# quadcopter.net
KiCad netlist of a schematic drawn in EAGLE
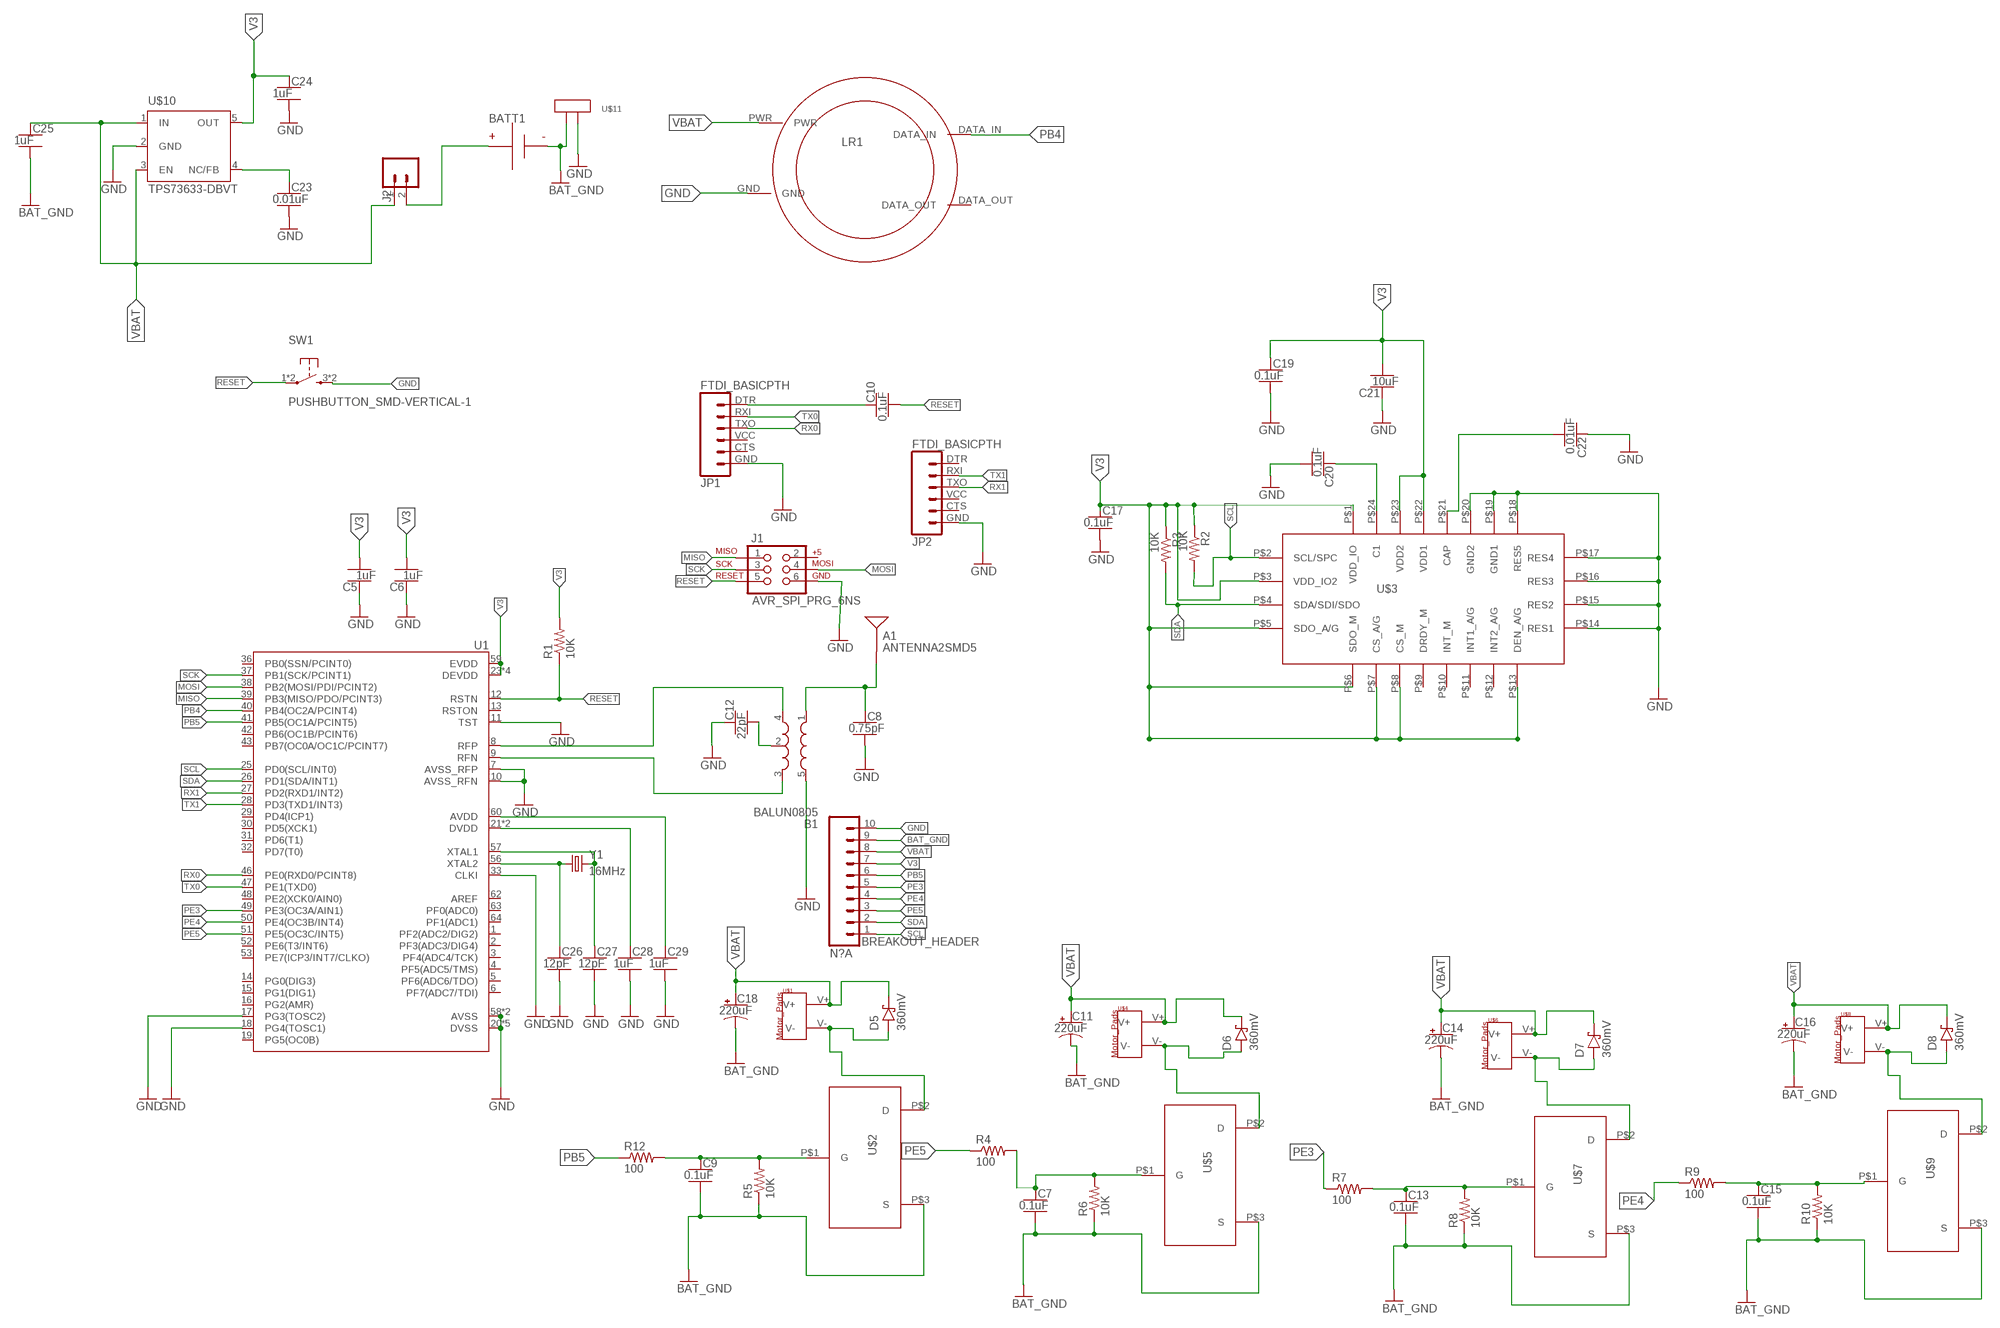
[diagram p0: schematic, sheet 1]

(export (version "E")
  (design (tool "Eeschema 10.0.6"))
  (components
    (comp (ref "A1")
      (value "ANTENNA2SMD5")
      (footprint "eagle-import:ANTENNA-CHIP5")
      (fields (field (name "MFR") "Linx Technologies Inc.") (field (name "MPN") "ANT-2.45-CHP-T"))
      (libsource (lib "eagle-import") (part "ANTENNA2SMD5"))
    )
    (comp (ref "B1")
      (value "BALUN0805")
      (footprint "eagle-import:BALUN")
      (fields (field (name "MFR") "Wurth Electronics Inc") (field (name "MPN") "748421245"))
      (libsource (lib "eagle-import") (part "BALUN0805"))
    )
    (comp (ref "BATT1")
      (value "BATTERY-HUBSAN-W/HOLDER")
      (footprint "eagle-import:BATTERY-W_HOLDER-380MAH-HUBSAN")
      (fields
        (field (name "MFR") "HUBSAN")
        (field (name "MPN") "X4-H107C-8-in-1")
        (field (name "CREATOR") "Swanson")
      )
      (libsource (lib "eagle-import") (part "BATTERY-HUBSAN-W/HOLDER"))
    )
    (comp (ref "BREAKOUT_HEADER")
      (value "N?A")
      (footprint "eagle-import:HDRV10W63P254_10X1_2540X254H838_HS")
      (fields (field (name "MFR") "Amphenol FCI") (field (name "MPN") "68000-110HLF"))
      (libsource (lib "eagle-import") (part "SIP-10_TH-254X10"))
    )
    (comp (ref "C5")
      (value "1uF")
      (footprint "eagle-import:CAPC2012X140_HS")
      (fields
        (field (name "MFR") "Murata Electronics North America")
        (field (name "MPN") "GRM21BR71H105KA12L")
      )
      (libsource (lib "eagle-import") (part "CAPACITOR-NP_SMD-2012-0805_CERAMIC-1UF"))
    )
    (comp (ref "C6")
      (value "1uF")
      (footprint "eagle-import:CAPC2012X140_HS")
      (fields
        (field (name "MFR") "Murata Electronics North America")
        (field (name "MPN") "GRM21BR71H105KA12L")
      )
      (libsource (lib "eagle-import") (part "CAPACITOR-NP_SMD-2012-0805_CERAMIC-1UF"))
    )
    (comp (ref "C7")
      (value "0.1uF")
      (footprint "eagle-import:CERAMIC_CAP_0805")
      (fields
        (field (name "MFR") "Murata Electronics North America")
        (field (name "MPN") "GRM21BR71H104KA01L")
        (field (name "CREATOR") "SWANSON")
      )
      (libsource (lib "eagle-import") (part "CERAMIC_CAP-0805-0.1UF"))
    )
    (comp (ref "C8")
      (value "0.75pF")
      (footprint "eagle-import:CAPC2012X140_HS")
      (fields
        (field (name "MFR") "Murata Electronics North America")
        (field (name "MPN") "GQM2195C2AR75CB01D")
      )
      (libsource (lib "eagle-import") (part "CAPACITOR-NP_SMD-2012-0805_CERAMIC-0.75PF"))
    )
    (comp (ref "C9")
      (value "0.1uF")
      (footprint "eagle-import:CERAMIC_CAP_0805")
      (fields
        (field (name "MFR") "Murata Electronics North America")
        (field (name "MPN") "GRM21BR71H104KA01L")
        (field (name "CREATOR") "SWANSON")
      )
      (libsource (lib "eagle-import") (part "CERAMIC_CAP-0805-0.1UF"))
    )
    (comp (ref "C10")
      (value "0.1uF")
      (footprint "eagle-import:CAPC2012X140_HS")
      (fields
        (field (name "MFR") "Murata Electronics North America")
        (field (name "MPN") "GRM21BR71H104KA01L")
      )
      (libsource (lib "eagle-import") (part "CAPACITOR-NP_SMD-2012-0805_CERAMIC-0.1UF"))
    )
    (comp (ref "C11")
      (value "220uF")
      (footprint "eagle-import:CAPMP7343X310_HS")
      (fields (field (name "MFR") "AVX Corporation") (field (name "MPN") "TAJD227K006RNJ"))
      (libsource (lib "eagle-import") (part "CAPACITOR-POL_SMD-7043-D_TANTALUM-220UF"))
    )
    (comp (ref "C12")
      (value "22pF")
      (footprint "eagle-import:CAPC2012X140_HS")
      (fields
        (field (name "MFR") "Murata Electronics North America")
        (field (name "MPN") "GRM21A5C2E220JW01D")
      )
      (libsource (lib "eagle-import") (part "CAPACITOR-NP_SMD-2012-0805_CERAMIC-22PF"))
    )
    (comp (ref "C13")
      (value "0.1uF")
      (footprint "eagle-import:CERAMIC_CAP_0805")
      (fields
        (field (name "MFR") "Murata Electronics North America")
        (field (name "MPN") "GRM21BR71H104KA01L")
        (field (name "CREATOR") "SWANSON")
      )
      (libsource (lib "eagle-import") (part "CERAMIC_CAP-0805-0.1UF"))
    )
    (comp (ref "C14")
      (value "220uF")
      (footprint "eagle-import:CAPMP7343X310_HS")
      (fields (field (name "MFR") "AVX Corporation") (field (name "MPN") "TAJD227K006RNJ"))
      (libsource (lib "eagle-import") (part "CAPACITOR-POL_SMD-7043-D_TANTALUM-220UF"))
    )
    (comp (ref "C15")
      (value "0.1uF")
      (footprint "eagle-import:CERAMIC_CAP_0805")
      (fields
        (field (name "MFR") "Murata Electronics North America")
        (field (name "MPN") "GRM21BR71H104KA01L")
        (field (name "CREATOR") "SWANSON")
      )
      (libsource (lib "eagle-import") (part "CERAMIC_CAP-0805-0.1UF"))
    )
    (comp (ref "C16")
      (value "220uF")
      (footprint "eagle-import:CAPMP7343X310_HS")
      (fields (field (name "MFR") "AVX Corporation") (field (name "MPN") "TAJD227K006RNJ"))
      (libsource (lib "eagle-import") (part "CAPACITOR-POL_SMD-7043-D_TANTALUM-220UF"))
    )
    (comp (ref "C17")
      (value "0.1uF")
      (footprint "eagle-import:CAPC2012X140_HS")
      (fields
        (field (name "MFR") "Murata Electronics North America")
        (field (name "MPN") "GRM21BR71H104KA01L")
      )
      (libsource (lib "eagle-import") (part "CAPACITOR-NP_SMD-2012-0805_CERAMIC-0.1UF"))
    )
    (comp (ref "C18")
      (value "220uF")
      (footprint "eagle-import:CAPMP7343X310_HS")
      (fields (field (name "MFR") "AVX Corporation") (field (name "MPN") "TAJD227K006RNJ"))
      (libsource (lib "eagle-import") (part "CAPACITOR-POL_SMD-7043-D_TANTALUM-220UF"))
    )
    (comp (ref "C19")
      (value "0.1uF")
      (footprint "eagle-import:CAPC2012X140_HS")
      (fields
        (field (name "MFR") "Murata Electronics North America")
        (field (name "MPN") "GRM21BR71H104KA01L")
      )
      (libsource (lib "eagle-import") (part "CAPACITOR-NP_SMD-2012-0805_CERAMIC-0.1UF"))
    )
    (comp (ref "C20")
      (value "0.1uF")
      (footprint "eagle-import:CAPC2012X140_HS")
      (fields
        (field (name "MFR") "Murata Electronics North America")
        (field (name "MPN") "GRM21BR71H104KA01L")
      )
      (libsource (lib "eagle-import") (part "CAPACITOR-NP_SMD-2012-0805_CERAMIC-0.1UF"))
    )
    (comp (ref "C21")
      (value "10uF")
      (footprint "eagle-import:CAPC2012X140_HS")
      (fields
        (field (name "MFR") "Murata Electronics North America")
        (field (name "MPN") "GRM21BR61E106KA73L")
      )
      (libsource (lib "eagle-import") (part "CAPACITOR-NP_SMD-2012-0805_CERAMIC-10UF"))
    )
    (comp (ref "C22")
      (value "0.01uF")
      (footprint "eagle-import:CAPC2012X140_HS")
      (fields
        (field (name "MFR") "Murata Electronics North America")
        (field (name "MPN") "GRM2195C1H103FA01D")
      )
      (libsource (lib "eagle-import") (part "CAPACITOR-NP_SMD-2012-0805_CERAMIC-0.01UF"))
    )
    (comp (ref "C23")
      (value "0.01uF")
      (footprint "eagle-import:CAPC2012X140_HS")
      (fields
        (field (name "MFR") "Murata Electronics North America")
        (field (name "MPN") "GRM2195C1H103FA01D")
      )
      (libsource (lib "eagle-import") (part "CAPACITOR-NP_SMD-2012-0805_CERAMIC-0.01UF"))
    )
    (comp (ref "C24")
      (value "1uF")
      (footprint "eagle-import:CAPC2012X140_HS")
      (fields
        (field (name "MFR") "Murata Electronics North America")
        (field (name "MPN") "GRM21BR71H105KA12L")
      )
      (libsource (lib "eagle-import") (part "CAPACITOR-NP_SMD-2012-0805_CERAMIC-1UF"))
    )
    (comp (ref "C25")
      (value "1uF")
      (footprint "eagle-import:CAPC2012X140_HS")
      (fields
        (field (name "MFR") "Murata Electronics North America")
        (field (name "MPN") "GRM21BR71H105KA12L")
      )
      (libsource (lib "eagle-import") (part "CAPACITOR-NP_SMD-2012-0805_CERAMIC-1UF"))
    )
    (comp (ref "C26")
      (value "12pF")
      (footprint "eagle-import:CAPC2012X140_HS")
      (fields
        (field (name "MFR") "Murata Electronics North America")
        (field (name "MPN") "GRM21A5C2E120JW01D")
      )
      (libsource (lib "eagle-import") (part "CAPACITOR-NP_SMD-2012-0805_CERAMIC-12PF"))
    )
    (comp (ref "C27")
      (value "12pF")
      (footprint "eagle-import:CAPC2012X140_HS")
      (fields
        (field (name "MFR") "Murata Electronics North America")
        (field (name "MPN") "GRM21A5C2E120JW01D")
      )
      (libsource (lib "eagle-import") (part "CAPACITOR-NP_SMD-2012-0805_CERAMIC-12PF"))
    )
    (comp (ref "C28")
      (value "1uF")
      (footprint "eagle-import:CAPC2012X140_HS")
      (fields
        (field (name "MFR") "Murata Electronics North America")
        (field (name "MPN") "GRM21BR71H105KA12L")
      )
      (libsource (lib "eagle-import") (part "CAPACITOR-NP_SMD-2012-0805_CERAMIC-1UF"))
    )
    (comp (ref "C29")
      (value "1uF")
      (footprint "eagle-import:CAPC2012X140_HS")
      (fields
        (field (name "MFR") "Murata Electronics North America")
        (field (name "MPN") "GRM21BR71H105KA12L")
      )
      (libsource (lib "eagle-import") (part "CAPACITOR-NP_SMD-2012-0805_CERAMIC-1UF"))
    )
    (comp (ref "D5")
      (value "360mV")
      (footprint "eagle-import:SOD3716X135_HS")
      (fields
        (field (name "MFR") "Toshiba Semiconductor and Storage")
        (field (name "MPN") "CRS08(TE85L,Q,M)")
      )
      (libsource (lib "eagle-import") (part "DIODE-SCHOTTKY_SMD-SOD123-360MV"))
    )
    (comp (ref "D6")
      (value "360mV")
      (footprint "eagle-import:SOD3716X135_HS")
      (fields
        (field (name "MFR") "Toshiba Semiconductor and Storage")
        (field (name "MPN") "CRS08(TE85L,Q,M)")
      )
      (libsource (lib "eagle-import") (part "DIODE-SCHOTTKY_SMD-SOD123-360MV"))
    )
    (comp (ref "D7")
      (value "360mV")
      (footprint "eagle-import:SOD3716X135_HS")
      (fields
        (field (name "MFR") "Toshiba Semiconductor and Storage")
        (field (name "MPN") "CRS08(TE85L,Q,M)")
      )
      (libsource (lib "eagle-import") (part "DIODE-SCHOTTKY_SMD-SOD123-360MV"))
    )
    (comp (ref "D8")
      (value "360mV")
      (footprint "eagle-import:SOD3716X135_HS")
      (fields
        (field (name "MFR") "Toshiba Semiconductor and Storage")
        (field (name "MPN") "CRS08(TE85L,Q,M)")
      )
      (libsource (lib "eagle-import") (part "DIODE-SCHOTTKY_SMD-SOD123-360MV"))
    )
    (comp (ref "J1")
      (value "AVR_SPI_PRG_6NS")
      (footprint "eagle-import:2X3-NS")
      (fields (field (name "MFR") "Amphenol FCI") (field (name "MPN") "67997-206HLF"))
      (libsource (lib "eagle-import") (part "AVR_SPI_PRG_6NS"))
    )
    (comp (ref "J2")
      (value "MALE_HEADER_2POS-2X1-0.1IN")
      (footprint "eagle-import:MALE_HEADER_2X1_0.1IN")
      (fields
        (field (name "MFR") "3M")
        (field (name "MPN") "961102-6404-AR")
        (field (name "CREATOR") "SWANSON")
      )
      (libsource (lib "eagle-import") (part "MALE_HEADER_2POS-2X1-0.1IN"))
    )
    (comp (ref "JP1")
      (value "FTDI_BASICPTH")
      (footprint "eagle-import:FTDI_BASIC")
      (fields (field (name "MFR") "Amphenol FCI") (field (name "MPN") "68016-406HLF"))
      (libsource (lib "eagle-import") (part "FTDI_BASICPTH"))
    )
    (comp (ref "JP2")
      (value "FTDI_BASICPTH")
      (footprint "eagle-import:FTDI_BASIC")
      (fields (field (name "MFR") "Amphenol FCI") (field (name "MPN") "68016-406HLF"))
      (libsource (lib "eagle-import") (part "FTDI_BASICPTH"))
    )
    (comp (ref "LR1")
      (value "LED_RING")
      (footprint "eagle-import:LED_RING")
      (fields
        (field (name "MFR") "Adafruit Industries LLC")
        (field (name "MPN") "1586")
        (field (name "CREATOR") "Zhe Wang")
      )
      (libsource (lib "eagle-import") (part "LED_RING"))
    )
    (comp (ref "R1")
      (value "10K")
      (footprint "eagle-import:RESC2012X60_HS")
      (fields (field (name "MFR") "Yageo") (field (name "MPN") "RC0805JR-0710KL"))
      (libsource (lib "eagle-import") (part "RESISTOR_SMD-2012-0805-10K"))
    )
    (comp (ref "R2")
      (value "10K")
      (footprint "eagle-import:RESC2012X60_HS")
      (fields (field (name "MFR") "Yageo") (field (name "MPN") "RC0805JR-0710KL"))
      (libsource (lib "eagle-import") (part "RESISTOR_SMD-2012-0805-10K"))
    )
    (comp (ref "R3")
      (value "10K")
      (footprint "eagle-import:RESC2012X60_HS")
      (fields (field (name "MFR") "Yageo") (field (name "MPN") "RC0805JR-0710KL"))
      (libsource (lib "eagle-import") (part "RESISTOR_SMD-2012-0805-10K"))
    )
    (comp (ref "R4")
      (value "100")
      (footprint "eagle-import:RESC2012X60_HS")
      (fields (field (name "MFR") "Yageo") (field (name "MPN") "RC0805JR-07100RL"))
      (libsource (lib "eagle-import") (part "RESISTOR_SMD-2012-0805-100"))
    )
    (comp (ref "R5")
      (value "10K")
      (footprint "eagle-import:RESC2012X60_HS")
      (fields (field (name "MFR") "Yageo") (field (name "MPN") "RC0805JR-0710KL"))
      (libsource (lib "eagle-import") (part "RESISTOR_SMD-2012-0805-10K"))
    )
    (comp (ref "R6")
      (value "10K")
      (footprint "eagle-import:RESC2012X60_HS")
      (fields (field (name "MFR") "Yageo") (field (name "MPN") "RC0805JR-0710KL"))
      (libsource (lib "eagle-import") (part "RESISTOR_SMD-2012-0805-10K"))
    )
    (comp (ref "R7")
      (value "100")
      (footprint "eagle-import:RESC2012X60_HS")
      (fields (field (name "MFR") "Yageo") (field (name "MPN") "RC0805JR-07100RL"))
      (libsource (lib "eagle-import") (part "RESISTOR_SMD-2012-0805-100"))
    )
    (comp (ref "R8")
      (value "10K")
      (footprint "eagle-import:RESC2012X60_HS")
      (fields (field (name "MFR") "Yageo") (field (name "MPN") "RC0805JR-0710KL"))
      (libsource (lib "eagle-import") (part "RESISTOR_SMD-2012-0805-10K"))
    )
    (comp (ref "R9")
      (value "100")
      (footprint "eagle-import:RESC2012X60_HS")
      (fields (field (name "MFR") "Yageo") (field (name "MPN") "RC0805JR-07100RL"))
      (libsource (lib "eagle-import") (part "RESISTOR_SMD-2012-0805-100"))
    )
    (comp (ref "R10")
      (value "10K")
      (footprint "eagle-import:RESC2012X60_HS")
      (fields (field (name "MFR") "Yageo") (field (name "MPN") "RC0805JR-0710KL"))
      (libsource (lib "eagle-import") (part "RESISTOR_SMD-2012-0805-10K"))
    )
    (comp (ref "R12")
      (value "100")
      (footprint "eagle-import:RESC2012X60_HS")
      (fields (field (name "MFR") "Yageo") (field (name "MPN") "RC0805JR-07100RL"))
      (libsource (lib "eagle-import") (part "RESISTOR_SMD-2012-0805-100"))
    )
    (comp (ref "SW1")
      (value "PUSHBUTTON_SMD-VERTICAL-1")
      (footprint "eagle-import:TE_FSM8JSMA_HS")
      (fields (field (name "MFR") "TE Connectivity Alcoswitch Switches") (field (name "MPN") "FSM4JSMA"))
      (libsource (lib "eagle-import") (part "PUSHBUTTON_SMD-VERTICAL-1"))
    )
    (comp (ref "U$1")
      (value "MOTOR_PADS")
      (footprint "eagle-import:MOTOR_PADS")
      (fields (field (name "MFR") "NA"))
      (libsource (lib "eagle-import") (part "MOTOR_PADS"))
    )
    (comp (ref "U$2")
      (value "N-CHANNEL_MOSFET")
      (footprint "eagle-import:N-CHANNELMOFSET")
      (fields
        (field (name "MFR") "Vishay Siliconix")
        (field (name "MPN") "SI2302CDS-T1-E3")
        (field (name "CREATOR") "Jason_Wong")
      )
      (libsource (lib "eagle-import") (part "N-CHANNEL_MOSFET"))
    )
    (comp (ref "U$3")
      (value "9-AXIS_IMU")
      (footprint "eagle-import:9-AXIS_IMU")
      (fields
        (field (name "MFR") "STMicroelectronics")
        (field (name "MPN") "LSM9DS1TR")
        (field (name "CREATOR") "Jason_Wong")
      )
      (libsource (lib "eagle-import") (part "9-AXIS_IMU"))
    )
    (comp (ref "U$4")
      (value "MOTOR_PADS")
      (footprint "eagle-import:MOTOR_PADS")
      (fields (field (name "MFR") "NA"))
      (libsource (lib "eagle-import") (part "MOTOR_PADS"))
    )
    (comp (ref "U$5")
      (value "N-CHANNEL_MOSFET")
      (footprint "eagle-import:N-CHANNELMOFSET")
      (fields
        (field (name "MFR") "Vishay Siliconix")
        (field (name "MPN") "SI2302CDS-T1-E3")
        (field (name "CREATOR") "Jason_Wong")
      )
      (libsource (lib "eagle-import") (part "N-CHANNEL_MOSFET"))
    )
    (comp (ref "U$6")
      (value "MOTOR_PADS")
      (footprint "eagle-import:MOTOR_PADS")
      (fields (field (name "MFR") "NA"))
      (libsource (lib "eagle-import") (part "MOTOR_PADS"))
    )
    (comp (ref "U$7")
      (value "N-CHANNEL_MOSFET")
      (footprint "eagle-import:N-CHANNELMOFSET")
      (fields
        (field (name "MFR") "Vishay Siliconix")
        (field (name "MPN") "SI2302CDS-T1-E3")
        (field (name "CREATOR") "Jason_Wong")
      )
      (libsource (lib "eagle-import") (part "N-CHANNEL_MOSFET"))
    )
    (comp (ref "U$8")
      (value "MOTOR_PADS")
      (footprint "eagle-import:MOTOR_PADS")
      (fields (field (name "MFR") "NA"))
      (libsource (lib "eagle-import") (part "MOTOR_PADS"))
    )
    (comp (ref "U$9")
      (value "N-CHANNEL_MOSFET")
      (footprint "eagle-import:N-CHANNELMOFSET")
      (fields
        (field (name "MFR") "Vishay Siliconix")
        (field (name "MPN") "SI2302CDS-T1-E3")
        (field (name "CREATOR") "Jason_Wong")
      )
      (libsource (lib "eagle-import") (part "N-CHANNEL_MOSFET"))
    )
    (comp (ref "U$10")
      (value "TPS73633-DBVT")
      (footprint "eagle-import:SOT23-DBV")
      (fields (field (name "MFR") "Texas Instruments") (field (name "MPN") "LP3985IM5X-3.0/NOPB"))
      (libsource (lib "eagle-import") (part "TPS73633-DBVT"))
    )
    (comp (ref "U$11")
      (value "NET_BRIDGE")
      (footprint "eagle-import:NET_BRIDGE")
      (fields
        (field (name "MFR") "NONE")
        (field (name "MPN") "123-456-789")
        (field (name "CREATOR") "Zhe")
        (field (name "REVIEWER") "NONE")
      )
      (libsource (lib "eagle-import") (part "NET_BRIDGE"))
    )
    (comp (ref "U1")
      (value "ATMEGA128RFA1")
      (footprint "eagle-import:QFN-64")
      (fields
        (field (name "MFR") "Atmel")
        (field (name "MPN") "ATMEGA128RFA1-ZUR00")
        (field (name "CREATOR") "Swanson")
      )
      (libsource (lib "eagle-import") (part "ATMEGA128RFA1"))
    )
    (comp (ref "Y1")
      (value "16MHz")
      (footprint "eagle-import:CRYSTAL-SMD-5X3")
      (fields (field (name "MFR") "Abracon LLC") (field (name "MPN") "ABM3B-16.000MHZ-B2-T"))
      (libsource (lib "eagle-import") (part "CRYSTAL5X3"))
    )
  )
  (nets
    (net (code "1") (name "BAT_GND") (class "Default")
      (node (ref "BATT1") (pin "-") (pinfunction "N_-") (pintype "bidirectional"))
      (node (ref "BREAKOUT_HEADER") (pin "9") (pinfunction "9_9") (pintype "passive"))
      (node (ref "C11") (pin "2") (pinfunction "-_2") (pintype "passive"))
      (node (ref "C13") (pin "2") (pinfunction "2_2") (pintype "passive"))
      (node (ref "C14") (pin "2") (pinfunction "-_2") (pintype "passive"))
      (node (ref "C15") (pin "2") (pinfunction "2_2") (pintype "passive"))
      (node (ref "C16") (pin "2") (pinfunction "-_2") (pintype "passive"))
      (node (ref "C18") (pin "2") (pinfunction "-_2") (pintype "passive"))
      (node (ref "C25") (pin "2") (pinfunction "2_2") (pintype "passive"))
      (node (ref "C7") (pin "2") (pinfunction "2_2") (pintype "passive"))
      (node (ref "C9") (pin "2") (pinfunction "2_2") (pintype "passive"))
      (node (ref "R10") (pin "1") (pinfunction "1_1") (pintype "passive"))
      (node (ref "R5") (pin "1") (pinfunction "1_1") (pintype "passive"))
      (node (ref "R6") (pin "1") (pinfunction "1_1") (pintype "passive"))
      (node (ref "R8") (pin "1") (pinfunction "1_1") (pintype "passive"))
      (node (ref "U$11") (pin "P$1") (pinfunction "P$1_P$1") (pintype "bidirectional"))
      (node (ref "U$2") (pin "P$3") (pinfunction "S_P$3") (pintype "bidirectional"))
      (node (ref "U$5") (pin "P$3") (pinfunction "S_P$3") (pintype "bidirectional"))
      (node (ref "U$7") (pin "P$3") (pinfunction "S_P$3") (pintype "bidirectional"))
      (node (ref "U$9") (pin "P$3") (pinfunction "S_P$3") (pintype "bidirectional"))
    )
    (net (code "2") (name "GND") (class "Default")
      (node (ref "B1") (pin "5") (pinfunction "GND_5") (pintype "bidirectional"))
      (node (ref "BREAKOUT_HEADER") (pin "10") (pinfunction "10_10") (pintype "passive"))
      (node (ref "C12") (pin "1") (pinfunction "1_1") (pintype "passive"))
      (node (ref "C17") (pin "2") (pinfunction "2_2") (pintype "passive"))
      (node (ref "C19") (pin "2") (pinfunction "2_2") (pintype "passive"))
      (node (ref "C20") (pin "2") (pinfunction "2_2") (pintype "passive"))
      (node (ref "C21") (pin "1") (pinfunction "1_1") (pintype "passive"))
      (node (ref "C22") (pin "1") (pinfunction "1_1") (pintype "passive"))
      (node (ref "C23") (pin "2") (pinfunction "2_2") (pintype "passive"))
      (node (ref "C24") (pin "2") (pinfunction "2_2") (pintype "passive"))
      (node (ref "C26") (pin "2") (pinfunction "2_2") (pintype "passive"))
      (node (ref "C27") (pin "2") (pinfunction "2_2") (pintype "passive"))
      (node (ref "C28") (pin "2") (pinfunction "2_2") (pintype "passive"))
      (node (ref "C29") (pin "2") (pinfunction "2_2") (pintype "passive"))
      (node (ref "C5") (pin "1") (pinfunction "1_1") (pintype "passive"))
      (node (ref "C6") (pin "1") (pinfunction "1_1") (pintype "passive"))
      (node (ref "C8") (pin "2") (pinfunction "2_2") (pintype "passive"))
      (node (ref "J1") (pin "6") (pinfunction "6_6") (pintype "passive"))
      (node (ref "JP1") (pin "GND") (pinfunction "6_GND") (pintype "passive"))
      (node (ref "JP2") (pin "GND") (pinfunction "6_GND") (pintype "passive"))
      (node (ref "LR1") (pin "GND") (pinfunction "GND_GND") (pintype "bidirectional"))
      (node (ref "SW1") (pin "3") (pinfunction "2_3") (pintype "passive"))
      (node (ref "SW1") (pin "4") (pinfunction "2_4") (pintype "passive"))
      (node (ref "U$10") (pin "2") (pinfunction "GND_2") (pintype "input"))
      (node (ref "U$11") (pin "P$2") (pinfunction "P$2_P$2") (pintype "bidirectional"))
      (node (ref "U$3") (pin "P$14") (pinfunction "RES1_P$14") (pintype "bidirectional"))
      (node (ref "U$3") (pin "P$15") (pinfunction "RES2_P$15") (pintype "bidirectional"))
      (node (ref "U$3") (pin "P$16") (pinfunction "RES3_P$16") (pintype "bidirectional"))
      (node (ref "U$3") (pin "P$17") (pinfunction "RES4_P$17") (pintype "bidirectional"))
      (node (ref "U$3") (pin "P$18") (pinfunction "RES5_P$18") (pintype "bidirectional"))
      (node (ref "U$3") (pin "P$19") (pinfunction "GND1_P$19") (pintype "bidirectional"))
      (node (ref "U$3") (pin "P$20") (pinfunction "GND2_P$20") (pintype "bidirectional"))
      (node (ref "U1") (pin "10") (pinfunction "AVSS_RFN_10") (pintype "bidirectional"))
      (node (ref "U1") (pin "11") (pinfunction "TST_11") (pintype "bidirectional"))
      (node (ref "U1") (pin "17") (pinfunction "PG3(TOSC2)_17") (pintype "bidirectional"))
      (node (ref "U1") (pin "18") (pinfunction "PG4(TOSC1)_18") (pintype "bidirectional"))
      (node (ref "U1") (pin "20") (pinfunction "DVSS_20") (pintype "bidirectional"))
      (node (ref "U1") (pin "24") (pinfunction "DVSS_24") (pintype "bidirectional"))
      (node (ref "U1") (pin "33") (pinfunction "CLKI_33") (pintype "bidirectional"))
      (node (ref "U1") (pin "35") (pinfunction "DVSS_35") (pintype "bidirectional"))
      (node (ref "U1") (pin "45") (pinfunction "DVSS_45") (pintype "bidirectional"))
      (node (ref "U1") (pin "55") (pinfunction "DVSS_55") (pintype "bidirectional"))
      (node (ref "U1") (pin "58") (pinfunction "AVSS_58") (pintype "bidirectional"))
      (node (ref "U1") (pin "61") (pinfunction "AVSS_61") (pintype "bidirectional"))
      (node (ref "U1") (pin "7") (pinfunction "AVSS_RFP_7") (pintype "bidirectional"))
    )
    (net (code "3") (name "MISO") (class "Default")
      (node (ref "J1") (pin "1") (pinfunction "1_1") (pintype "passive"))
      (node (ref "U1") (pin "39") (pinfunction "PB3(MISO/PDO/PCINT3)_39") (pintype "bidirectional"))
    )
    (net (code "4") (name "MOSI") (class "Default")
      (node (ref "J1") (pin "4") (pinfunction "4_4") (pintype "passive"))
      (node (ref "U1") (pin "38") (pinfunction "PB2(MOSI/PDI/PCINT2)_38") (pintype "bidirectional"))
    )
    (net (code "5") (name "Net-(A1-SIGNAL)") (class "Default")
      (node (ref "A1") (pin "FEED") (pinfunction "SIGNAL_FEED") (pintype "bidirectional"))
      (node (ref "B1") (pin "1") (pinfunction "IN_1") (pintype "bidirectional"))
      (node (ref "C8") (pin "1") (pinfunction "1_1") (pintype "passive"))
    )
    (net (code "6") (name "Net-(B1-GND-Pad2)") (class "Default")
      (node (ref "B1") (pin "2") (pinfunction "GND_2") (pintype "bidirectional"))
      (node (ref "C12") (pin "2") (pinfunction "2_2") (pintype "passive"))
    )
    (net (code "7") (name "Net-(B1-OUT1)") (class "Default")
      (node (ref "B1") (pin "4") (pinfunction "OUT1_4") (pintype "bidirectional"))
      (node (ref "U1") (pin "8") (pinfunction "RFP_8") (pintype "bidirectional"))
    )
    (net (code "8") (name "Net-(B1-OUT2)") (class "Default")
      (node (ref "B1") (pin "3") (pinfunction "OUT2_3") (pintype "bidirectional"))
      (node (ref "U1") (pin "9") (pinfunction "RFN_9") (pintype "bidirectional"))
    )
    (net (code "9") (name "Net-(BATT1-P)") (class "Default")
      (node (ref "BATT1") (pin "+") (pinfunction "P_+") (pintype "bidirectional"))
      (node (ref "J2") (pin "2") (pinfunction "2_2") (pintype "passive"))
    )
    (net (code "10") (name "Net-(C28-Pad1)") (class "Default")
      (node (ref "C28") (pin "1") (pinfunction "1_1") (pintype "passive"))
      (node (ref "U1") (pin "21") (pinfunction "DVDD_21") (pintype "bidirectional"))
      (node (ref "U1") (pin "22") (pinfunction "DVDD_22") (pintype "bidirectional"))
    )
    (net (code "11") (name "Net-(JP1-1)") (class "Default")
      (node (ref "C10") (pin "1") (pinfunction "1_1") (pintype "passive"))
      (node (ref "JP1") (pin "DTR") (pinfunction "1_DTR") (pintype "passive"))
    )
    (net (code "12") (name "Net-(U$2-D)") (class "Default")
      (node (ref "D5") (pin "A") (pinfunction "A_A") (pintype "passive"))
      (node (ref "U$1") (pin "V-") (pinfunction "V-_V-") (pintype "bidirectional"))
      (node (ref "U$2") (pin "P$2") (pinfunction "D_P$2") (pintype "bidirectional"))
    )
    (net (code "13") (name "Net-(U$2-G)") (class "Default")
      (node (ref "C9") (pin "1") (pinfunction "1_1") (pintype "passive"))
      (node (ref "R12") (pin "2") (pinfunction "2_2") (pintype "passive"))
      (node (ref "R5") (pin "2") (pinfunction "2_2") (pintype "passive"))
      (node (ref "U$2") (pin "P$1") (pinfunction "G_P$1") (pintype "bidirectional"))
    )
    (net (code "14") (name "Net-(U$3-C1)") (class "Default")
      (node (ref "C20") (pin "1") (pinfunction "1_1") (pintype "passive"))
      (node (ref "U$3") (pin "P$24") (pinfunction "C1_P$24") (pintype "bidirectional"))
    )
    (net (code "15") (name "Net-(U$3-CAP)") (class "Default")
      (node (ref "C22") (pin "2") (pinfunction "2_2") (pintype "passive"))
      (node (ref "U$3") (pin "P$21") (pinfunction "CAP_P$21") (pintype "bidirectional"))
    )
    (net (code "16") (name "Net-(U$5-D)") (class "Default")
      (node (ref "D6") (pin "A") (pinfunction "A_A") (pintype "passive"))
      (node (ref "U$4") (pin "V-") (pinfunction "V-_V-") (pintype "bidirectional"))
      (node (ref "U$5") (pin "P$2") (pinfunction "D_P$2") (pintype "bidirectional"))
    )
    (net (code "17") (name "Net-(U$5-G)") (class "Default")
      (node (ref "C7") (pin "1") (pinfunction "1_1") (pintype "passive"))
      (node (ref "R4") (pin "2") (pinfunction "2_2") (pintype "passive"))
      (node (ref "R6") (pin "2") (pinfunction "2_2") (pintype "passive"))
      (node (ref "U$5") (pin "P$1") (pinfunction "G_P$1") (pintype "bidirectional"))
    )
    (net (code "18") (name "Net-(U$7-D)") (class "Default")
      (node (ref "D7") (pin "A") (pinfunction "A_A") (pintype "passive"))
      (node (ref "U$6") (pin "V-") (pinfunction "V-_V-") (pintype "bidirectional"))
      (node (ref "U$7") (pin "P$2") (pinfunction "D_P$2") (pintype "bidirectional"))
    )
    (net (code "19") (name "Net-(U$7-G)") (class "Default")
      (node (ref "C13") (pin "1") (pinfunction "1_1") (pintype "passive"))
      (node (ref "R7") (pin "2") (pinfunction "2_2") (pintype "passive"))
      (node (ref "R8") (pin "2") (pinfunction "2_2") (pintype "passive"))
      (node (ref "U$7") (pin "P$1") (pinfunction "G_P$1") (pintype "bidirectional"))
    )
    (net (code "20") (name "Net-(U$9-D)") (class "Default")
      (node (ref "D8") (pin "A") (pinfunction "A_A") (pintype "passive"))
      (node (ref "U$8") (pin "V-") (pinfunction "V-_V-") (pintype "bidirectional"))
      (node (ref "U$9") (pin "P$2") (pinfunction "D_P$2") (pintype "bidirectional"))
    )
    (net (code "21") (name "Net-(U$9-G)") (class "Default")
      (node (ref "C15") (pin "1") (pinfunction "1_1") (pintype "passive"))
      (node (ref "R10") (pin "2") (pinfunction "2_2") (pintype "passive"))
      (node (ref "R9") (pin "2") (pinfunction "2_2") (pintype "passive"))
      (node (ref "U$9") (pin "P$1") (pinfunction "G_P$1") (pintype "bidirectional"))
    )
    (net (code "22") (name "Net-(U$10-NC{slash}FB)") (class "Default")
      (node (ref "C23") (pin "1") (pinfunction "1_1") (pintype "passive"))
      (node (ref "U$10") (pin "4") (pinfunction "NC/FB_4") (pintype "passive"))
    )
    (net (code "23") (name "Net-(U1-AVDD)") (class "Default")
      (node (ref "C29") (pin "1") (pinfunction "1_1") (pintype "passive"))
      (node (ref "U1") (pin "60") (pinfunction "AVDD_60") (pintype "bidirectional"))
    )
    (net (code "24") (name "Net-(U1-XTAL1)") (class "Default")
      (node (ref "C27") (pin "1") (pinfunction "1_1") (pintype "passive"))
      (node (ref "U1") (pin "57") (pinfunction "XTAL1_57") (pintype "bidirectional"))
      (node (ref "Y1") (pin "3") (pinfunction "2_3") (pintype "passive"))
    )
    (net (code "25") (name "Net-(U1-XTAL2)") (class "Default")
      (node (ref "C26") (pin "1") (pinfunction "1_1") (pintype "passive"))
      (node (ref "U1") (pin "56") (pinfunction "XTAL2_56") (pintype "bidirectional"))
      (node (ref "Y1") (pin "1") (pinfunction "1_1") (pintype "passive"))
    )
    (net (code "26") (name "PB4") (class "Default")
      (node (ref "LR1") (pin "DATA_IN") (pinfunction "DATA_IN_DATA_IN") (pintype "bidirectional"))
      (node (ref "U1") (pin "40") (pinfunction "PB4(OC2A/PCINT4)_40") (pintype "bidirectional"))
    )
    (net (code "27") (name "PB5") (class "Default")
      (node (ref "BREAKOUT_HEADER") (pin "6") (pinfunction "6_6") (pintype "passive"))
      (node (ref "R12") (pin "1") (pinfunction "1_1") (pintype "passive"))
      (node (ref "U1") (pin "41") (pinfunction "PB5(OC1A/PCINT5)_41") (pintype "bidirectional"))
    )
    (net (code "28") (name "PE3") (class "Default")
      (node (ref "BREAKOUT_HEADER") (pin "5") (pinfunction "5_5") (pintype "passive"))
      (node (ref "R7") (pin "1") (pinfunction "1_1") (pintype "passive"))
      (node (ref "U1") (pin "49") (pinfunction "PE3(OC3A/AIN1)_49") (pintype "bidirectional"))
    )
    (net (code "29") (name "PE4") (class "Default")
      (node (ref "BREAKOUT_HEADER") (pin "4") (pinfunction "4_4") (pintype "passive"))
      (node (ref "R9") (pin "1") (pinfunction "1_1") (pintype "passive"))
      (node (ref "U1") (pin "50") (pinfunction "PE4(OC3B/INT4)_50") (pintype "bidirectional"))
    )
    (net (code "30") (name "PE5") (class "Default")
      (node (ref "BREAKOUT_HEADER") (pin "3") (pinfunction "3_3") (pintype "passive"))
      (node (ref "R4") (pin "1") (pinfunction "1_1") (pintype "passive"))
      (node (ref "U1") (pin "51") (pinfunction "PE5(OC3C/INT5)_51") (pintype "bidirectional"))
    )
    (net (code "31") (name "RESET") (class "Default")
      (node (ref "C10") (pin "2") (pinfunction "2_2") (pintype "passive"))
      (node (ref "J1") (pin "5") (pinfunction "5_5") (pintype "passive"))
      (node (ref "R1") (pin "1") (pinfunction "1_1") (pintype "passive"))
      (node (ref "SW1") (pin "1") (pinfunction "1_1") (pintype "passive"))
      (node (ref "SW1") (pin "2") (pinfunction "1_2") (pintype "passive"))
      (node (ref "U1") (pin "12") (pinfunction "RSTN_12") (pintype "bidirectional"))
    )
    (net (code "32") (name "RX0") (class "Default")
      (node (ref "JP1") (pin "TXO") (pinfunction "3_TXO") (pintype "passive"))
      (node (ref "U1") (pin "46") (pinfunction "PE0(RXD0/PCINT8)_46") (pintype "bidirectional"))
    )
    (net (code "33") (name "RX1") (class "Default")
      (node (ref "JP2") (pin "TXO") (pinfunction "3_TXO") (pintype "passive"))
      (node (ref "U1") (pin "27") (pinfunction "PD2(RXD1/INT2)_27") (pintype "bidirectional"))
    )
    (net (code "34") (name "SCK") (class "Default")
      (node (ref "J1") (pin "3") (pinfunction "3_3") (pintype "passive"))
      (node (ref "U1") (pin "37") (pinfunction "PB1(SCK/PCINT1)_37") (pintype "bidirectional"))
    )
    (net (code "35") (name "SCL") (class "Default")
      (node (ref "BREAKOUT_HEADER") (pin "1") (pinfunction "1_1") (pintype "passive"))
      (node (ref "R2") (pin "2") (pinfunction "2_2") (pintype "passive"))
      (node (ref "U$3") (pin "P$2") (pinfunction "SCL/SPC_P$2") (pintype "bidirectional"))
      (node (ref "U1") (pin "25") (pinfunction "PD0(SCL/INT0)_25") (pintype "bidirectional"))
    )
    (net (code "36") (name "SDA") (class "Default")
      (node (ref "BREAKOUT_HEADER") (pin "2") (pinfunction "2_2") (pintype "passive"))
      (node (ref "R3") (pin "2") (pinfunction "2_2") (pintype "passive"))
      (node (ref "U$3") (pin "P$4") (pinfunction "SDA/SDI/SDO_P$4") (pintype "bidirectional"))
      (node (ref "U1") (pin "26") (pinfunction "PD1(SDA/INT1)_26") (pintype "bidirectional"))
    )
    (net (code "37") (name "TX0") (class "Default")
      (node (ref "JP1") (pin "RXI") (pinfunction "2_RXI") (pintype "passive"))
      (node (ref "U1") (pin "47") (pinfunction "PE1(TXD0)_47") (pintype "bidirectional"))
    )
    (net (code "38") (name "TX1") (class "Default")
      (node (ref "JP2") (pin "RXI") (pinfunction "2_RXI") (pintype "passive"))
      (node (ref "U1") (pin "28") (pinfunction "PD3(TXD1/INT3)_28") (pintype "bidirectional"))
    )
    (net (code "39") (name "V3") (class "Default")
      (node (ref "BREAKOUT_HEADER") (pin "7") (pinfunction "7_7") (pintype "passive"))
      (node (ref "C17") (pin "1") (pinfunction "1_1") (pintype "passive"))
      (node (ref "C19") (pin "1") (pinfunction "1_1") (pintype "passive"))
      (node (ref "C21") (pin "2") (pinfunction "2_2") (pintype "passive"))
      (node (ref "C24") (pin "1") (pinfunction "1_1") (pintype "passive"))
      (node (ref "C5") (pin "2") (pinfunction "2_2") (pintype "passive"))
      (node (ref "C6") (pin "2") (pinfunction "2_2") (pintype "passive"))
      (node (ref "R1") (pin "2") (pinfunction "2_2") (pintype "passive"))
      (node (ref "R2") (pin "1") (pinfunction "1_1") (pintype "passive"))
      (node (ref "R3") (pin "1") (pinfunction "1_1") (pintype "passive"))
      (node (ref "U$10") (pin "5") (pinfunction "OUT_5") (pintype "passive"))
      (node (ref "U$3") (pin "P$1") (pinfunction "VDD_IO_P$1") (pintype "bidirectional"))
      (node (ref "U$3") (pin "P$13") (pinfunction "DEN_A/G_P$13") (pintype "bidirectional"))
      (node (ref "U$3") (pin "P$22") (pinfunction "VDD1_P$22") (pintype "bidirectional"))
      (node (ref "U$3") (pin "P$23") (pinfunction "VDD2_P$23") (pintype "bidirectional"))
      (node (ref "U$3") (pin "P$3") (pinfunction "VDD_IO2_P$3") (pintype "bidirectional"))
      (node (ref "U$3") (pin "P$5") (pinfunction "SDO_A/G_P$5") (pintype "bidirectional"))
      (node (ref "U$3") (pin "P$6") (pinfunction "SDO_M_P$6") (pintype "bidirectional"))
      (node (ref "U$3") (pin "P$7") (pinfunction "CS_A/G_P$7") (pintype "bidirectional"))
      (node (ref "U$3") (pin "P$8") (pinfunction "CS_M_P$8") (pintype "bidirectional"))
      (node (ref "U1") (pin "23") (pinfunction "DEVDD_23") (pintype "bidirectional"))
      (node (ref "U1") (pin "34") (pinfunction "DEVDD_34") (pintype "bidirectional"))
      (node (ref "U1") (pin "44") (pinfunction "DEVDD_44") (pintype "bidirectional"))
      (node (ref "U1") (pin "54") (pinfunction "DEVDD_54") (pintype "bidirectional"))
      (node (ref "U1") (pin "59") (pinfunction "EVDD_59") (pintype "bidirectional"))
    )
    (net (code "40") (name "VBAT") (class "Default")
      (node (ref "BREAKOUT_HEADER") (pin "8") (pinfunction "8_8") (pintype "passive"))
      (node (ref "C11") (pin "1") (pinfunction "+_1") (pintype "passive"))
      (node (ref "C14") (pin "1") (pinfunction "+_1") (pintype "passive"))
      (node (ref "C16") (pin "1") (pinfunction "+_1") (pintype "passive"))
      (node (ref "C18") (pin "1") (pinfunction "+_1") (pintype "passive"))
      (node (ref "C25") (pin "1") (pinfunction "1_1") (pintype "passive"))
      (node (ref "D5") (pin "C") (pinfunction "C_C") (pintype "passive"))
      (node (ref "D6") (pin "C") (pinfunction "C_C") (pintype "passive"))
      (node (ref "D7") (pin "C") (pinfunction "C_C") (pintype "passive"))
      (node (ref "D8") (pin "C") (pinfunction "C_C") (pintype "passive"))
      (node (ref "J2") (pin "1") (pinfunction "1_1") (pintype "passive"))
      (node (ref "LR1") (pin "PWR") (pinfunction "PWR_PWR") (pintype "bidirectional"))
      (node (ref "U$1") (pin "V+") (pinfunction "V+_V+") (pintype "bidirectional"))
      (node (ref "U$10") (pin "1") (pinfunction "IN_1") (pintype "input"))
      (node (ref "U$10") (pin "3") (pinfunction "EN_3") (pintype "input"))
      (node (ref "U$4") (pin "V+") (pinfunction "V+_V+") (pintype "bidirectional"))
      (node (ref "U$6") (pin "V+") (pinfunction "V+_V+") (pintype "bidirectional"))
      (node (ref "U$8") (pin "V+") (pinfunction "V+_V+") (pintype "bidirectional"))
    )
    (net (code "41") (name "unconnected-(J1-Pad2)") (class "Default")
      (node (ref "J1") (pin "2") (pinfunction "2_2") (pintype "passive"))
    )
    (net (code "42") (name "unconnected-(JP1-4-PadVCC)") (class "Default")
      (node (ref "JP1") (pin "VCC") (pinfunction "4_VCC") (pintype "passive"))
    )
    (net (code "43") (name "unconnected-(JP1-5-PadCTS)") (class "Default")
      (node (ref "JP1") (pin "CTS") (pinfunction "5_CTS") (pintype "passive"))
    )
    (net (code "44") (name "unconnected-(JP2-1-PadDTR)") (class "Default")
      (node (ref "JP2") (pin "DTR") (pinfunction "1_DTR") (pintype "passive"))
    )
    (net (code "45") (name "unconnected-(JP2-4-PadVCC)") (class "Default")
      (node (ref "JP2") (pin "VCC") (pinfunction "4_VCC") (pintype "passive"))
    )
    (net (code "46") (name "unconnected-(JP2-5-PadCTS)") (class "Default")
      (node (ref "JP2") (pin "CTS") (pinfunction "5_CTS") (pintype "passive"))
    )
    (net (code "47") (name "unconnected-(LR1-PadDATA_OUT)") (class "Default")
      (node (ref "LR1") (pin "DATA_OUT") (pinfunction "DATA_OUT_DATA_OUT") (pintype "bidirectional"))
    )
    (net (code "48") (name "unconnected-(U$3-DRDY_M-PadP$9)") (class "Default")
      (node (ref "U$3") (pin "P$9") (pinfunction "DRDY_M_P$9") (pintype "bidirectional"))
    )
    (net (code "49") (name "unconnected-(U$3-INT1_A{slash}G-PadP$11)") (class "Default")
      (node (ref "U$3") (pin "P$11") (pinfunction "INT1_A/G_P$11") (pintype "bidirectional"))
    )
    (net (code "50") (name "unconnected-(U$3-INT2_A{slash}G-PadP$12)") (class "Default")
      (node (ref "U$3") (pin "P$12") (pinfunction "INT2_A/G_P$12") (pintype "bidirectional"))
    )
    (net (code "51") (name "unconnected-(U$3-INT_M-PadP$10)") (class "Default")
      (node (ref "U$3") (pin "P$10") (pinfunction "INT_M_P$10") (pintype "bidirectional"))
    )
    (net (code "52") (name "unconnected-(U1-AREF-Pad62)") (class "Default")
      (node (ref "U1") (pin "62") (pinfunction "AREF_62") (pintype "bidirectional"))
    )
    (net (code "53") (name "unconnected-(U1-PB0(SSN{slash}PCINT0)-Pad36)") (class "Default")
      (node (ref "U1") (pin "36") (pinfunction "PB0(SSN/PCINT0)_36") (pintype "bidirectional"))
    )
    (net (code "54") (name "unconnected-(U1-PB6(OC1B{slash}PCINT6)-Pad42)") (class "Default")
      (node (ref "U1") (pin "42") (pinfunction "PB6(OC1B/PCINT6)_42") (pintype "bidirectional"))
    )
    (net (code "55") (name "unconnected-(U1-PB7(OC0A{slash}OC1C{slash}PCINT7)-Pad43)") (class "Default")
      (node (ref "U1") (pin "43") (pinfunction "PB7(OC0A/OC1C/PCINT7)_43") (pintype "bidirectional"))
    )
    (net (code "56") (name "unconnected-(U1-PD4(ICP1)-Pad29)") (class "Default")
      (node (ref "U1") (pin "29") (pinfunction "PD4(ICP1)_29") (pintype "bidirectional"))
    )
    (net (code "57") (name "unconnected-(U1-PD5(XCK1)-Pad30)") (class "Default")
      (node (ref "U1") (pin "30") (pinfunction "PD5(XCK1)_30") (pintype "bidirectional"))
    )
    (net (code "58") (name "unconnected-(U1-PD6(T1)-Pad31)") (class "Default")
      (node (ref "U1") (pin "31") (pinfunction "PD6(T1)_31") (pintype "bidirectional"))
    )
    (net (code "59") (name "unconnected-(U1-PD7(T0)-Pad32)") (class "Default")
      (node (ref "U1") (pin "32") (pinfunction "PD7(T0)_32") (pintype "bidirectional"))
    )
    (net (code "60") (name "unconnected-(U1-PE2(XCK0{slash}AIN0)-Pad48)") (class "Default")
      (node (ref "U1") (pin "48") (pinfunction "PE2(XCK0/AIN0)_48") (pintype "bidirectional"))
    )
    (net (code "61") (name "unconnected-(U1-PE6(T3{slash}INT6)-Pad52)") (class "Default")
      (node (ref "U1") (pin "52") (pinfunction "PE6(T3/INT6)_52") (pintype "bidirectional"))
    )
    (net (code "62") (name "unconnected-(U1-PE7(ICP3{slash}INT7{slash}CLKO)-Pad53)") (class "Default")
      (node (ref "U1") (pin "53") (pinfunction "PE7(ICP3/INT7/CLKO)_53") (pintype "bidirectional"))
    )
    (net (code "63") (name "unconnected-(U1-PF0(ADC0)-Pad63)") (class "Default")
      (node (ref "U1") (pin "63") (pinfunction "PF0(ADC0)_63") (pintype "bidirectional"))
    )
    (net (code "64") (name "unconnected-(U1-PF1(ADC1)-Pad64)") (class "Default")
      (node (ref "U1") (pin "64") (pinfunction "PF1(ADC1)_64") (pintype "bidirectional"))
    )
    (net (code "65") (name "unconnected-(U1-PF2(ADC2{slash}DIG2)-Pad1)") (class "Default")
      (node (ref "U1") (pin "1") (pinfunction "PF2(ADC2/DIG2)_1") (pintype "bidirectional"))
    )
    (net (code "66") (name "unconnected-(U1-PF3(ADC3{slash}DIG4)-Pad2)") (class "Default")
      (node (ref "U1") (pin "2") (pinfunction "PF3(ADC3/DIG4)_2") (pintype "bidirectional"))
    )
    (net (code "67") (name "unconnected-(U1-PF4(ADC4{slash}TCK)-Pad3)") (class "Default")
      (node (ref "U1") (pin "3") (pinfunction "PF4(ADC4/TCK)_3") (pintype "bidirectional"))
    )
    (net (code "68") (name "unconnected-(U1-PF5(ADC5{slash}TMS)-Pad4)") (class "Default")
      (node (ref "U1") (pin "4") (pinfunction "PF5(ADC5/TMS)_4") (pintype "bidirectional"))
    )
    (net (code "69") (name "unconnected-(U1-PF6(ADC6{slash}TDO)-Pad5)") (class "Default")
      (node (ref "U1") (pin "5") (pinfunction "PF6(ADC6/TDO)_5") (pintype "bidirectional"))
    )
    (net (code "70") (name "unconnected-(U1-PF7(ADC7{slash}TDI)-Pad6)") (class "Default")
      (node (ref "U1") (pin "6") (pinfunction "PF7(ADC7/TDI)_6") (pintype "bidirectional"))
    )
    (net (code "71") (name "unconnected-(U1-PG0(DIG3)-Pad14)") (class "Default")
      (node (ref "U1") (pin "14") (pinfunction "PG0(DIG3)_14") (pintype "bidirectional"))
    )
    (net (code "72") (name "unconnected-(U1-PG1(DIG1)-Pad15)") (class "Default")
      (node (ref "U1") (pin "15") (pinfunction "PG1(DIG1)_15") (pintype "bidirectional"))
    )
    (net (code "73") (name "unconnected-(U1-PG2(AMR)-Pad16)") (class "Default")
      (node (ref "U1") (pin "16") (pinfunction "PG2(AMR)_16") (pintype "bidirectional"))
    )
    (net (code "74") (name "unconnected-(U1-PG5(OC0B)-Pad19)") (class "Default")
      (node (ref "U1") (pin "19") (pinfunction "PG5(OC0B)_19") (pintype "bidirectional"))
    )
    (net (code "75") (name "unconnected-(U1-RSTON-Pad13)") (class "Default")
      (node (ref "U1") (pin "13") (pinfunction "RSTON_13") (pintype "bidirectional"))
    )
  )
)
